# Telliskivi2014MainBoardPower.net
KiCad netlist of a schematic drawn in Altium Designer
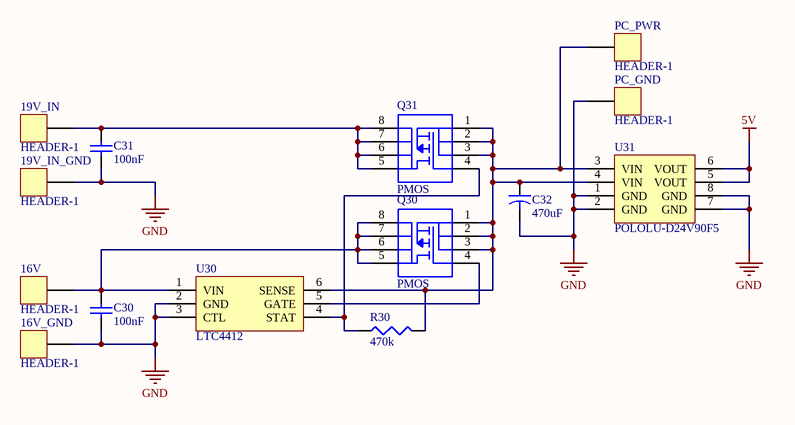
[diagram p0: Telliskivi2014MainBoardPower.SchDoc]

(export (version "E")
  (design (tool "Eeschema 10.0.6"))
  (components
    (comp (ref "16V") (value "HEADER-1") (footprint "POWER-VIA") (libsource (lib "") (part "HEADER-1_1")))
    (comp (ref "16V_GND") (value "HEADER-1") (footprint "POWER-VIA") (libsource (lib "") (part "HEADER-1_1")))
    (comp (ref "19V_IN") (value "HEADER-1") (footprint "POWER-VIA") (libsource (lib "") (part "HEADER-1_1")))
    (comp (ref "19V_IN_GND")
      (value "HEADER-1")
      (footprint "POWER-VIA")
      (libsource (lib "") (part "HEADER-1_1"))
    )
    (comp (ref "C30")
      (value "100nF")
      (footprint "1608[0603]")
      (description "Capacitor (Semiconductor SIM Model)")
      (fields (field (name "PUBLISHER") "Altium Limited"))
      (libsource (lib "Miscellaneous Devices") (part "Cap Semi"))
    )
    (comp (ref "C31")
      (value "100nF")
      (footprint "1608[0603]")
      (description "Capacitor (Semiconductor SIM Model)")
      (fields (field (name "PUBLISHER") "Altium Limited"))
      (libsource (lib "Miscellaneous Devices") (part "Cap Semi"))
    )
    (comp (ref "C32")
      (value "470uF")
      (footprint "CAPR5-4X5")
      (description "Capacitor")
      (fields (field (name "PUBLISHER") "Altium Limited"))
      (libsource (lib "Miscellaneous Devices") (part "Cap2"))
    )
    (comp (ref "PC_GND")
      (value "HEADER-1")
      (footprint "POWER-VIA")
      (libsource (lib "connectors") (part "HEADER-1"))
    )
    (comp (ref "PC_PWR")
      (value "HEADER-1")
      (footprint "POWER-VIA")
      (libsource (lib "connectors") (part "HEADER-1"))
    )
    (comp (ref "Q30") (value "PMOS") (footprint "SO8") (libsource (lib "misc") (part "PMOS")))
    (comp (ref "Q31") (value "PMOS") (footprint "SO8") (libsource (lib "misc") (part "PMOS")))
    (comp (ref "R30")
      (value "470k")
      (footprint "J1-0603")
      (description "Resistor")
      (fields (field (name "PUBLISHER") "Altium Limited"))
      (libsource (lib "Miscellaneous Devices") (part "Res3"))
    )
    (comp (ref "U30") (value "LTC4412") (footprint "TSOT-23-6") (libsource (lib "digital") (part "LTC4412")))
    (comp (ref "U31")
      (value "POLOLU-D24V90F5")
      (footprint "POLOLU-D24V90F5-NO-OUTLINE")
      (libsource (lib "power") (part "POLOLU-D24V90F5"))
    )
  )
  (nets
    (net (code "1") (name "5V") (class "Default")
      (node (ref "U31") (pin "5") (pinfunction "VOUT_5") (pintype "passive"))
      (node (ref "U31") (pin "6") (pinfunction "VOUT_6") (pintype "passive"))
    )
    (net (code "2") (name "GND") (class "Default")
      (node (ref "16V_GND") (pin "1") (pinfunction "1_1") (pintype "passive"))
      (node (ref "19V_IN_GND") (pin "1") (pinfunction "1_1") (pintype "passive"))
      (node (ref "C30") (pin "2") (pinfunction "2_2") (pintype "passive"))
      (node (ref "C31") (pin "2") (pinfunction "2_2") (pintype "passive"))
      (node (ref "C32") (pin "2") (pinfunction "2_2") (pintype "passive"))
      (node (ref "PC_GND") (pin "1") (pinfunction "1_1") (pintype "passive"))
      (node (ref "U30") (pin "2") (pinfunction "GND_2") (pintype "passive"))
      (node (ref "U30") (pin "3") (pinfunction "CTL_3") (pintype "passive"))
      (node (ref "U31") (pin "1") (pinfunction "GND_1") (pintype "passive"))
      (node (ref "U31") (pin "2") (pinfunction "GND_2") (pintype "passive"))
      (node (ref "U31") (pin "7") (pinfunction "GND_7") (pintype "passive"))
      (node (ref "U31") (pin "8") (pinfunction "GND_8") (pintype "passive"))
    )
    (net (code "3") (name "Net-(19V_IN-Pad1)") (class "Default")
      (node (ref "19V_IN") (pin "1") (pinfunction "1_1") (pintype "passive"))
      (node (ref "C31") (pin "1") (pinfunction "1_1") (pintype "passive"))
      (node (ref "Q31") (pin "5") (pinfunction "5_5") (pintype "passive"))
      (node (ref "Q31") (pin "6") (pinfunction "6_6") (pintype "passive"))
      (node (ref "Q31") (pin "7") (pinfunction "7_7") (pintype "passive"))
      (node (ref "Q31") (pin "8") (pinfunction "8_8") (pintype "passive"))
    )
    (net (code "4") (name "Net-(U30-GATE)") (class "Default")
      (node (ref "Q30") (pin "4") (pinfunction "4_4") (pintype "passive"))
      (node (ref "U30") (pin "5") (pinfunction "GATE_5") (pintype "passive"))
    )
    (net (code "5") (name "Net-(U30-SENSE)") (class "Default")
      (node (ref "C32") (pin "1") (pinfunction "1_1") (pintype "passive"))
      (node (ref "PC_PWR") (pin "1") (pinfunction "1_1") (pintype "passive"))
      (node (ref "Q30") (pin "1") (pinfunction "1_1") (pintype "passive"))
      (node (ref "Q30") (pin "2") (pinfunction "2_2") (pintype "passive"))
      (node (ref "Q30") (pin "3") (pinfunction "3_3") (pintype "passive"))
      (node (ref "Q31") (pin "1") (pinfunction "1_1") (pintype "passive"))
      (node (ref "Q31") (pin "2") (pinfunction "2_2") (pintype "passive"))
      (node (ref "Q31") (pin "3") (pinfunction "3_3") (pintype "passive"))
      (node (ref "R30") (pin "2") (pinfunction "2_2") (pintype "passive"))
      (node (ref "U30") (pin "6") (pinfunction "SENSE_6") (pintype "passive"))
      (node (ref "U31") (pin "3") (pinfunction "VIN_3") (pintype "passive"))
      (node (ref "U31") (pin "4") (pinfunction "VIN_4") (pintype "passive"))
    )
    (net (code "6") (name "Net-(U30-STAT)") (class "Default")
      (node (ref "Q31") (pin "4") (pinfunction "4_4") (pintype "passive"))
      (node (ref "R30") (pin "1") (pinfunction "1_1") (pintype "passive"))
      (node (ref "U30") (pin "4") (pinfunction "STAT_4") (pintype "passive"))
    )
    (net (code "7") (name "Net-(U30-VIN)") (class "Default")
      (node (ref "16V") (pin "1") (pinfunction "1_1") (pintype "passive"))
      (node (ref "C30") (pin "1") (pinfunction "1_1") (pintype "passive"))
      (node (ref "Q30") (pin "5") (pinfunction "5_5") (pintype "passive"))
      (node (ref "Q30") (pin "6") (pinfunction "6_6") (pintype "passive"))
      (node (ref "Q30") (pin "7") (pinfunction "7_7") (pintype "passive"))
      (node (ref "Q30") (pin "8") (pinfunction "8_8") (pintype "passive"))
      (node (ref "U30") (pin "1") (pinfunction "VIN_1") (pintype "passive"))
    )
  )
)
